# SPSGRFCsheet.net
KiCad netlist of a schematic drawn in Altium Designer
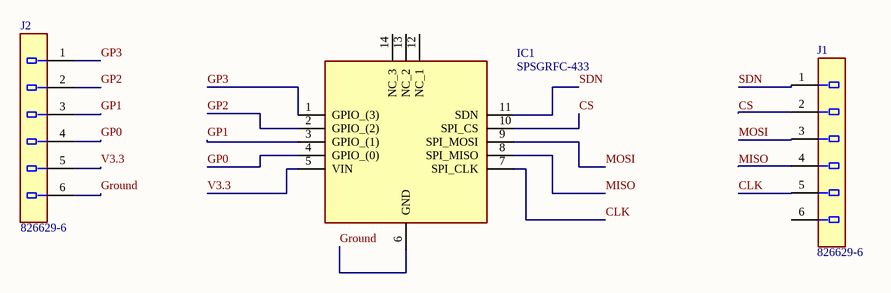
[diagram p0: SPSGRFCsheet.SchDoc]

(export (version "E")
  (design (tool "Eeschema 10.0.6"))
  (components
    (comp (ref "IC1")
      (value "SPSGRFC-433")
      (footprint "SamacSys:SPSGRFC433")
      (description "Integrated Circuit")
      (fields (field (name "MOUSER PART NUMBER") "511-SPSGRFC-433"))
      (libsource (lib "SamacSys") (part "SPSGRFC-433"))
    )
    (comp (ref "J1")
      (value "Conn_TE_826629-6_eec")
      (footprint "TE_C-826629_0")
      (description "CONN HEADER BRKWAWAY 6POS AU")
      (fields
        (field (name "PART NUMBER") "826629-6")
        (field (name "MANUFACTURER") "TE")
        (field (name "MOUSER PART NUMBER") "571-826629-6")
      )
      (libsource (lib "") (part "Conn_TE_826629-6_eec_1"))
    )
    (comp (ref "J2")
      (value "Conn_TE_826629-6_eec")
      (footprint "TE_C-826629_0")
      (description "CONN HEADER BRKWAWAY 6POS AU")
      (fields
        (field (name "PART NUMBER") "826629-6")
        (field (name "MANUFACTURER") "TE")
        (field (name "MOUSER PART NUMBER") "571-826629-6")
      )
      (libsource (lib "Conn_TE_826629-6_eec") (part "Conn_TE_826629-6_eec"))
    )
  )
  (nets
    (net (code "1") (name "/CLK") (class "Default")
      (node (ref "IC1") (pin "7") (pinfunction "SPI_CLK_7") (pintype "passive"))
      (node (ref "J1") (pin "5") (pinfunction "5_5") (pintype "passive"))
    )
    (net (code "2") (name "/CS") (class "Default")
      (node (ref "IC1") (pin "10") (pinfunction "SPI_CS_10") (pintype "passive"))
      (node (ref "J1") (pin "2") (pinfunction "2_2") (pintype "passive"))
    )
    (net (code "3") (name "/GP0") (class "Default")
      (node (ref "IC1") (pin "4") (pinfunction "GPIO_(0)_4") (pintype "passive"))
      (node (ref "J2") (pin "4") (pinfunction "4_4") (pintype "passive"))
    )
    (net (code "4") (name "/GP1") (class "Default")
      (node (ref "IC1") (pin "3") (pinfunction "GPIO_(1)_3") (pintype "passive"))
      (node (ref "J2") (pin "3") (pinfunction "3_3") (pintype "passive"))
    )
    (net (code "5") (name "/GP2") (class "Default")
      (node (ref "IC1") (pin "2") (pinfunction "GPIO_(2)_2") (pintype "passive"))
      (node (ref "J2") (pin "2") (pinfunction "2_2") (pintype "passive"))
    )
    (net (code "6") (name "/GP3") (class "Default")
      (node (ref "IC1") (pin "1") (pinfunction "GPIO_(3)_1") (pintype "passive"))
      (node (ref "J2") (pin "1") (pinfunction "1_1") (pintype "passive"))
    )
    (net (code "7") (name "/Ground") (class "Default")
      (node (ref "IC1") (pin "6") (pinfunction "GND_6") (pintype "passive"))
      (node (ref "J2") (pin "6") (pinfunction "6_6") (pintype "passive"))
    )
    (net (code "8") (name "/MISO") (class "Default")
      (node (ref "IC1") (pin "8") (pinfunction "SPI_MISO_8") (pintype "passive"))
      (node (ref "J1") (pin "4") (pinfunction "4_4") (pintype "passive"))
    )
    (net (code "9") (name "/MOSI") (class "Default")
      (node (ref "IC1") (pin "9") (pinfunction "SPI_MOSI_9") (pintype "passive"))
      (node (ref "J1") (pin "3") (pinfunction "3_3") (pintype "passive"))
    )
    (net (code "10") (name "/SDN") (class "Default")
      (node (ref "IC1") (pin "11") (pinfunction "SDN_11") (pintype "passive"))
      (node (ref "J1") (pin "1") (pinfunction "1_1") (pintype "passive"))
    )
    (net (code "11") (name "/V3.3") (class "Default")
      (node (ref "IC1") (pin "5") (pinfunction "VIN_5") (pintype "passive"))
      (node (ref "J2") (pin "5") (pinfunction "5_5") (pintype "passive"))
    )
    (net (code "12") (name "unconnected-(IC1-NC_1-Pad12)") (class "Default")
      (node (ref "IC1") (pin "12") (pinfunction "NC_1_12") (pintype "passive"))
    )
    (net (code "13") (name "unconnected-(IC1-NC_2-Pad13)") (class "Default")
      (node (ref "IC1") (pin "13") (pinfunction "NC_2_13") (pintype "passive"))
    )
    (net (code "14") (name "unconnected-(IC1-NC_3-Pad14)") (class "Default")
      (node (ref "IC1") (pin "14") (pinfunction "NC_3_14") (pintype "passive"))
    )
    (net (code "15") (name "unconnected-(J1-Pad6)") (class "Default")
      (node (ref "J1") (pin "6") (pinfunction "6_6") (pintype "passive"))
    )
  )
)
